# HomeController.net
KiCad netlist of a schematic drawn in Altium Designer
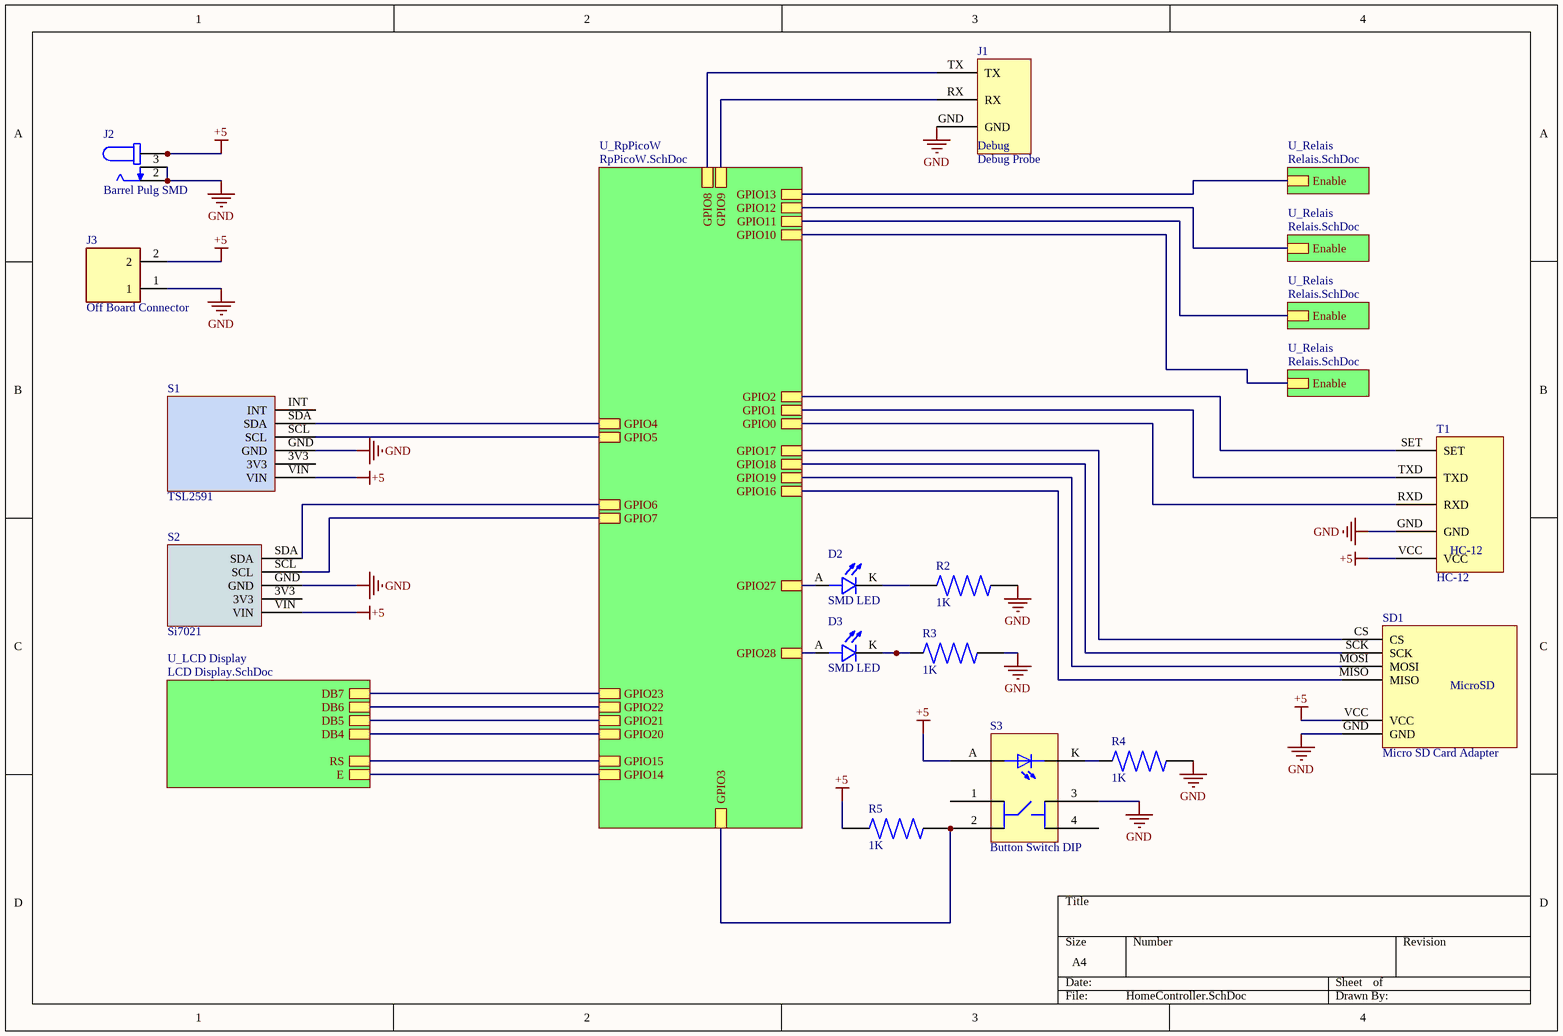
[diagram p0: HomeController.SchDoc]

(export (version "E")
  (design (tool "Eeschema 10.0.6"))
  (components
    (comp (ref "D2")
      (value "SMD LED")
      (footprint "SMD LED-Footprint-1")
      (description "Generic SMD LED")
      (libsource (lib "Tobias") (part "SMD LED-Symbol-1"))
    )
    (comp (ref "D3")
      (value "SMD LED")
      (footprint "SMD LED-Footprint-1")
      (description "Generic SMD LED")
      (libsource (lib "Tobias") (part "SMD LED-Symbol-1"))
    )
    (comp (ref "J1")
      (value "Debug Probe")
      (footprint "Debug Probe-Footprint-1")
      (description "A Connector for the Debug Probe")
      (libsource (lib "Tobias") (part "Debug Probe-Symbol-1"))
    )
    (comp (ref "J2")
      (value "Barrel Pulg SMD")
      (footprint "Barrel Pulg SMD-Footprint-1")
      (description "SMD Barrel Plug")
      (libsource (lib "Tobias") (part "Barrel Pulg SMD-Symbol-1"))
    )
    (comp (ref "J3")
      (value "Off Board Connector")
      (footprint "Off Board Connector-Footprint-1")
      (description "2 Pin")
      (libsource (lib "Tobias") (part "Off Board Connector-Symbol-1"))
    )
    (comp (ref "R2")
      (value "1K")
      (footprint "SMD Resistor-Footprint-1")
      (description "Generic SMD Resistor")
      (libsource (lib "Tobias") (part "SMD Resistor-Symbol-1"))
    )
    (comp (ref "R3")
      (value "1K")
      (footprint "SMD Resistor-Footprint-1")
      (description "Generic SMD Resistor")
      (libsource (lib "Tobias") (part "SMD Resistor-Symbol-1"))
    )
    (comp (ref "R4")
      (value "1K")
      (footprint "SMD Resistor-Footprint-1")
      (description "Generic SMD Resistor")
      (libsource (lib "Tobias") (part "SMD Resistor-Symbol-1"))
    )
    (comp (ref "R5")
      (value "1K")
      (footprint "SMD Resistor-Footprint-1")
      (description "Generic SMD Resistor")
      (libsource (lib "Tobias") (part "SMD Resistor-Symbol-1"))
    )
    (comp (ref "S1")
      (value "TSL2591")
      (footprint "TSL2591-Footprint-1")
      (description "Adafruit High Dynamic Range Digital Light Sensor")
      (libsource (lib "Tobias") (part "TSL2591-Symbol-1"))
    )
    (comp (ref "S2")
      (value "Si7021")
      (footprint "Si7021-Footprint-1")
      (description "Adafruit Si7021 Temperature & Humidity Sensor")
      (libsource (lib "Tobias") (part "Si7021-Symbol-1"))
    )
    (comp (ref "S3")
      (value "Button Switch DIP")
      (footprint "Button Switch DIP -Footprint-1")
      (description "6 Pin with LED")
      (libsource (lib "Tobias") (part "Button Switch DIP -Symbol-1"))
    )
    (comp (ref "SD1")
      (value "Micro SD Card Adapter")
      (footprint "Micro SD Card Adapter-Footprint-1")
      (description "SD Card Break Out Board")
      (libsource (lib "Tobias") (part "Micro SD Card Adapter-Symbol-1"))
    )
    (comp (ref "T1")
      (value "HC-12")
      (footprint "HC-12-Footprint-1")
      (description "UART Telemetry Antenna")
      (libsource (lib "Tobias") (part "HC-12-Symbol-1"))
    )
  )
  (nets
    (net (code "1") (name "+5") (class "Default")
      (node (ref "J2") (pin "1A") (pinfunction "1_1A") (pintype "passive"))
      (node (ref "J2") (pin "1B") (pinfunction "1_1B") (pintype "passive"))
      (node (ref "J3") (pin "2") (pinfunction "2_2") (pintype "passive"))
      (node (ref "R5") (pin "1") (pinfunction "1_1") (pintype "passive"))
      (node (ref "S1") (pin "VIN") (pinfunction "VIN_VIN") (pintype "passive"))
      (node (ref "S2") (pin "VIN") (pinfunction "VIN_VIN") (pintype "passive"))
      (node (ref "S3") (pin "A") (pinfunction "A_A") (pintype "passive"))
      (node (ref "SD1") (pin "VCC") (pinfunction "VCC_VCC") (pintype "passive"))
      (node (ref "T1") (pin "VCC") (pinfunction "VCC_VCC") (pintype "passive"))
    )
    (net (code "11") (name "/GPIO0") (class "Default")
      (node (ref "T1") (pin "RXD") (pinfunction "RXD_RXD") (pintype "passive"))
    )
    (net (code "12") (name "/GPIO1") (class "Default")
      (node (ref "T1") (pin "TXD") (pinfunction "TXD_TXD") (pintype "passive"))
    )
    (net (code "13") (name "/GPIO2") (class "Default")
      (node (ref "T1") (pin "SET") (pinfunction "SET_SET") (pintype "passive"))
    )
    (net (code "14") (name "/GPIO3") (class "Default")
      (node (ref "R5") (pin "2") (pinfunction "2_2") (pintype "passive"))
      (node (ref "S3") (pin "2") (pinfunction "2_2") (pintype "passive"))
    )
    (net (code "15") (name "/GPIO4") (class "Default")
      (node (ref "S1") (pin "SDA") (pinfunction "SDA_SDA") (pintype "passive"))
    )
    (net (code "16") (name "/GPIO5") (class "Default")
      (node (ref "S1") (pin "SCL") (pinfunction "SCL_SCL") (pintype "passive"))
    )
    (net (code "17") (name "/GPIO6") (class "Default")
      (node (ref "S2") (pin "SDA") (pinfunction "SDA_SDA") (pintype "passive"))
    )
    (net (code "18") (name "/GPIO7") (class "Default")
      (node (ref "S2") (pin "SCL") (pinfunction "SCL_SCL") (pintype "passive"))
    )
    (net (code "19") (name "/GPIO8") (class "Default")
      (node (ref "J1") (pin "TX") (pinfunction "TX_TX") (pintype "passive"))
    )
    (net (code "20") (name "/GPIO9") (class "Default")
      (node (ref "J1") (pin "RX") (pinfunction "RX_RX") (pintype "passive"))
    )
    (net (code "22") (name "/GPIO16") (class "Default")
      (node (ref "SD1") (pin "MISO") (pinfunction "MISO_MISO") (pintype "passive"))
    )
    (net (code "23") (name "/GPIO17") (class "Default")
      (node (ref "SD1") (pin "CS") (pinfunction "CS_CS") (pintype "passive"))
    )
    (net (code "24") (name "/GPIO18") (class "Default")
      (node (ref "SD1") (pin "SCK") (pinfunction "SCK_SCK") (pintype "passive"))
    )
    (net (code "25") (name "/GPIO19") (class "Default")
      (node (ref "SD1") (pin "MOSI") (pinfunction "MOSI_MOSI") (pintype "passive"))
    )
    (net (code "26") (name "/GPIO27") (class "Default")
      (node (ref "D2") (pin "A") (pinfunction "A_A") (pintype "passive"))
    )
    (net (code "27") (name "/GPIO28") (class "Default")
      (node (ref "D3") (pin "A") (pinfunction "A_A") (pintype "passive"))
    )
    (net (code "28") (name "GND") (class "Default")
      (node (ref "J1") (pin "GND") (pinfunction "GND_GND") (pintype "passive"))
      (node (ref "J2") (pin "2") (pinfunction "2_2") (pintype "passive"))
      (node (ref "J2") (pin "3") (pinfunction "3_3") (pintype "passive"))
      (node (ref "J3") (pin "1") (pinfunction "1_1") (pintype "passive"))
      (node (ref "R2") (pin "2") (pinfunction "2_2") (pintype "passive"))
      (node (ref "R3") (pin "2") (pinfunction "2_2") (pintype "passive"))
      (node (ref "R4") (pin "2") (pinfunction "2_2") (pintype "passive"))
      (node (ref "S1") (pin "GND") (pinfunction "GND_GND") (pintype "passive"))
      (node (ref "S2") (pin "GND") (pinfunction "GND_GND") (pintype "passive"))
      (node (ref "S3") (pin "3") (pinfunction "3_3") (pintype "passive"))
      (node (ref "SD1") (pin "GND") (pinfunction "GND_GND") (pintype "passive"))
      (node (ref "T1") (pin "GND") (pinfunction "GND_GND") (pintype "passive"))
    )
    (net (code "29") (name "Net-(D2-C)") (class "Default")
      (node (ref "D2") (pin "K") (pinfunction "C_K") (pintype "passive"))
      (node (ref "R2") (pin "1") (pinfunction "1_1") (pintype "passive"))
    )
    (net (code "30") (name "Net-(D3-C)") (class "Default")
      (node (ref "D3") (pin "K") (pinfunction "C_K") (pintype "passive"))
      (node (ref "R3") (pin "1") (pinfunction "1_1") (pintype "passive"))
    )
    (net (code "31") (name "Net-(R4-Pad1)") (class "Default")
      (node (ref "R4") (pin "1") (pinfunction "1_1") (pintype "passive"))
      (node (ref "S3") (pin "K") (pinfunction "K_K") (pintype "passive"))
    )
    (net (code "32") (name "unconnected-(S1-Pad3V3)") (class "Default")
      (node (ref "S1") (pin "3V3") (pinfunction "3V3_3V3") (pintype "passive"))
    )
    (net (code "33") (name "unconnected-(S1-PadINT)") (class "Default")
      (node (ref "S1") (pin "INT") (pinfunction "INT_INT") (pintype "passive"))
    )
    (net (code "34") (name "unconnected-(S2-Pad3V3)") (class "Default")
      (node (ref "S2") (pin "3V3") (pinfunction "3V3_3V3") (pintype "passive"))
    )
    (net (code "35") (name "unconnected-(S3-Pad1)") (class "Default")
      (node (ref "S3") (pin "1") (pinfunction "1_1") (pintype "passive"))
    )
    (net (code "36") (name "unconnected-(S3-Pad4)") (class "Default")
      (node (ref "S3") (pin "4") (pinfunction "4_4") (pintype "passive"))
    )
  )
)
